# Motors.net
KiCad netlist of a schematic drawn in Altium Designer
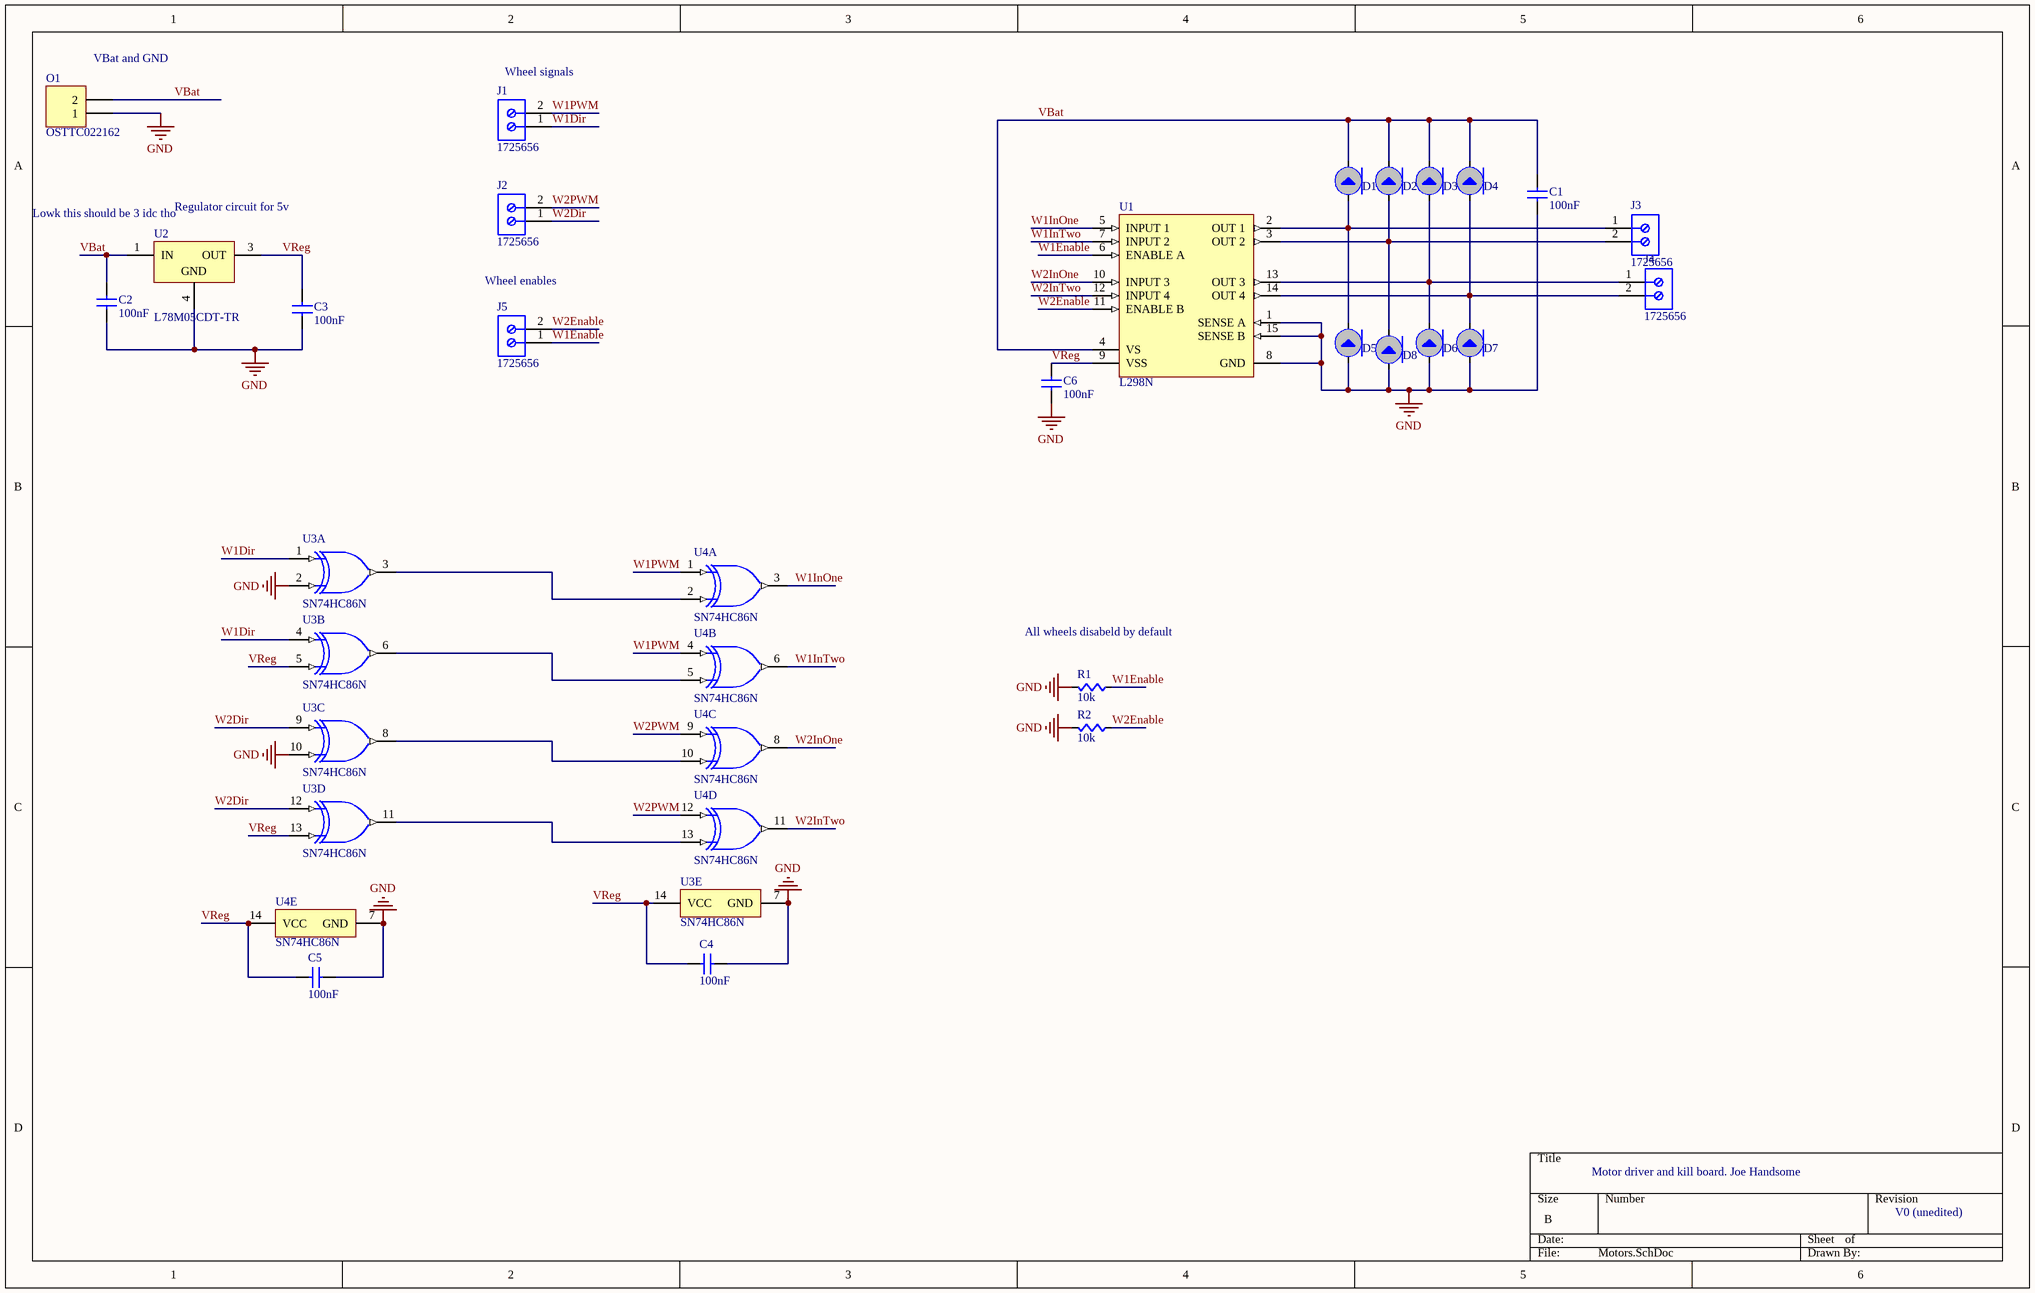
[diagram p0: Motors.SchDoc]

(export (version "E")
  (design (tool "Eeschema 10.0.6"))
  (components
    (comp (ref "C1")
      (value "100nF")
      (footprint "CAPC0603")
      (fields (field (name "Comment") "Cap"))
      (libsource (lib "Passives") (part "Cap"))
    )
    (comp (ref "C2")
      (value "100nF")
      (footprint "CAPC0603")
      (fields (field (name "Comment") "Cap"))
      (libsource (lib "Passives") (part "Cap"))
    )
    (comp (ref "C3")
      (value "100nF")
      (footprint "CAPC0603")
      (fields (field (name "Comment") "Cap"))
      (libsource (lib "Passives") (part "Cap"))
    )
    (comp (ref "C4")
      (value "100nF")
      (footprint "CAPC0603")
      (fields (field (name "Comment") "Cap"))
      (libsource (lib "Passives") (part "Cap"))
    )
    (comp (ref "C5")
      (value "100nF")
      (footprint "CAPC0603")
      (fields (field (name "Comment") "Cap"))
      (libsource (lib "Passives") (part "Cap"))
    )
    (comp (ref "C6")
      (value "100nF")
      (footprint "CAPC0603")
      (fields (field (name "Comment") "Cap"))
      (libsource (lib "Passives") (part "Cap"))
    )
    (comp (ref "D1")
      (value "Diode")
      (footprint "MBRS360SMB")
      (description "Standard Diode Template")
      (libsource (lib "Semiconductors") (part "Diode"))
    )
    (comp (ref "D2")
      (value "Diode")
      (footprint "MBRS360SMB")
      (description "Standard Diode Template")
      (libsource (lib "Semiconductors") (part "Diode"))
    )
    (comp (ref "D3")
      (value "Diode")
      (footprint "MBRS360SMB")
      (description "Standard Diode Template")
      (libsource (lib "Semiconductors") (part "Diode"))
    )
    (comp (ref "D4")
      (value "Diode")
      (footprint "MBRS360SMB")
      (description "Standard Diode Template")
      (libsource (lib "Semiconductors") (part "Diode"))
    )
    (comp (ref "D5")
      (value "Diode")
      (footprint "MBRS360SMB")
      (description "Standard Diode Template")
      (libsource (lib "Semiconductors") (part "Diode"))
    )
    (comp (ref "D6")
      (value "Diode")
      (footprint "MBRS360SMB")
      (description "Standard Diode Template")
      (libsource (lib "Semiconductors") (part "Diode"))
    )
    (comp (ref "D7")
      (value "Diode")
      (footprint "MBRS360SMB")
      (description "Standard Diode Template")
      (libsource (lib "Semiconductors") (part "Diode"))
    )
    (comp (ref "D8")
      (value "Diode")
      (footprint "MBRS360SMB")
      (description "Standard Diode Template")
      (libsource (lib "Semiconductors") (part "Diode"))
    )
    (comp (ref "J1")
      (value "1725656")
      (footprint "PHOE-1725656-2")
      (description "Male Header, Pitch 2.54 mm, 1 x 2 Position, Height 9 mm, Tail Length 3.5 mm")
      (fields (field (name "MANUFACTURER") "Phoenix Contact"))
      (libsource (lib "Altium Content Vault") (part "CN-1P-F-TB2"))
    )
    (comp (ref "J2")
      (value "1725656")
      (footprint "PHOE-1725656-2")
      (description "Male Header, Pitch 2.54 mm, 1 x 2 Position, Height 9 mm, Tail Length 3.5 mm")
      (fields (field (name "MANUFACTURER") "Phoenix Contact"))
      (libsource (lib "Altium Content Vault") (part "CN-1P-F-TB2"))
    )
    (comp (ref "J3")
      (value "1725656")
      (footprint "PHOE-1725656-2")
      (description "Male Header, Pitch 2.54 mm, 1 x 2 Position, Height 9 mm, Tail Length 3.5 mm")
      (fields (field (name "MANUFACTURER") "Phoenix Contact"))
      (libsource (lib "Altium Content Vault") (part "CN-1P-F-TB2"))
    )
    (comp (ref "J4")
      (value "1725656")
      (footprint "PHOE-1725656-2")
      (description "Male Header, Pitch 2.54 mm, 1 x 2 Position, Height 9 mm, Tail Length 3.5 mm")
      (fields (field (name "MANUFACTURER") "Phoenix Contact"))
      (libsource (lib "Altium Content Vault") (part "CN-1P-F-TB2"))
    )
    (comp (ref "J5")
      (value "1725656")
      (footprint "PHOE-1725656-2")
      (description "Male Header, Pitch 2.54 mm, 1 x 2 Position, Height 9 mm, Tail Length 3.5 mm")
      (fields (field (name "MANUFACTURER") "Phoenix Contact"))
      (libsource (lib "Altium Content Vault") (part "CN-1P-F-TB2"))
    )
    (comp (ref "O1")
      (value "OSTTC022162")
      (footprint "high_amp_conn")
      (description "Terminal Block Header 2-Position Top Screw 0.200\" (5.08mm) PC-Pins")
      (fields (field (name "MANUFACTURER") "On-Shore Technology") (field (name "VOLTAGE") "300V"))
      (libsource (lib "Schlib1") (part "OSTTC022162"))
    )
    (comp (ref "R1")
      (value "10k")
      (footprint "RES0603")
      (fields (field (name "Comment") "Res"))
      (libsource (lib "Passives") (part "Res"))
    )
    (comp (ref "R2")
      (value "10k")
      (footprint "RES0603")
      (fields (field (name "Comment") "Res"))
      (libsource (lib "Passives") (part "Res"))
    )
    (comp (ref "U1")
      (value "L298N")
      (footprint "STM-FM-15")
      (description "Dual Full-Bridge Driver, 4.8 to 46 V, -40 to 150 degC, 15-Pin FM (MW 15L), RoHS, Tube")
      (fields (field (name "MANUFACTURER") "STMicroelectronics") (field (name "PARTNUMBER") "L298"))
      (libsource (lib "Altium Content Vault") (part "STM-L298-15"))
    )
    (comp (ref "U2")
      (value "L78M05CDT-TR")
      (footprint "TO-252_L")
      (description "Positive Voltage Regulator, 5V, 3-Pin DPAK, Tape and Reel")
      (libsource (lib "Altium Content Vault") (part "PM-REG-L4940-SOT3"))
    )
    (comp (ref "U3")
      (value "SN74HC86N")
      (footprint "PCBComponent_1")
      (description "Quadruple 2-Input Exclusive-OR Gates, N0014A, TUBE")
      (fields
        (field (name "MANUFACTURER") "Texas Instruments")
        (field (name "GENERIC PART NUMBER") "SN74HC86")
      )
      (libsource (lib "Schlib1") (part "CMP-0778-00109-3"))
    )
    (comp (ref "U4")
      (value "SN74HC86N")
      (footprint "PCBComponent_1")
      (description "Quadruple 2-Input Exclusive-OR Gates, N0014A, TUBE")
      (fields
        (field (name "MANUFACTURER") "Texas Instruments")
        (field (name "GENERIC PART NUMBER") "SN74HC86")
      )
      (libsource (lib "Schlib1") (part "CMP-0778-00109-3"))
    )
  )
  (nets
    (net (code "1") (name "/VBat") (class "Default")
      (node (ref "C1") (pin "1") (pinfunction "A_1") (pintype "passive"))
      (node (ref "C2") (pin "1") (pinfunction "A_1") (pintype "passive"))
      (node (ref "D1") (pin "C") (pinfunction "C_C") (pintype "passive"))
      (node (ref "D2") (pin "C") (pinfunction "C_C") (pintype "passive"))
      (node (ref "D3") (pin "C") (pinfunction "C_C") (pintype "passive"))
      (node (ref "D4") (pin "C") (pinfunction "C_C") (pintype "passive"))
      (node (ref "O1") (pin "2") (pinfunction "2_2") (pintype "passive"))
      (node (ref "U1") (pin "4") (pinfunction "VS_4") (pintype "power_in"))
      (node (ref "U2") (pin "1") (pinfunction "IN_1") (pintype "power_in"))
    )
    (net (code "2") (name "/VReg") (class "Default")
      (node (ref "C3") (pin "1") (pinfunction "A_1") (pintype "passive"))
      (node (ref "C4") (pin "1") (pinfunction "A_1") (pintype "passive"))
      (node (ref "C5") (pin "1") (pinfunction "A_1") (pintype "passive"))
      (node (ref "C6") (pin "1") (pinfunction "A_1") (pintype "passive"))
      (node (ref "U1") (pin "9") (pinfunction "VSS_9") (pintype "power_in"))
      (node (ref "U2") (pin "3") (pinfunction "OUT_3") (pintype "power_in"))
      (node (ref "U3") (pin "13") (pinfunction "4B_13") (pintype "input"))
      (node (ref "U3") (pin "14") (pinfunction "VCC_14") (pintype "power_in"))
      (node (ref "U3") (pin "5") (pinfunction "2B_5") (pintype "input"))
      (node (ref "U4") (pin "14") (pinfunction "VCC_14") (pintype "power_in"))
    )
    (net (code "3") (name "/W1Dir") (class "Default")
      (node (ref "J1") (pin "1") (pinfunction "1_1") (pintype "passive"))
      (node (ref "U3") (pin "1") (pinfunction "1A_1") (pintype "input"))
      (node (ref "U3") (pin "4") (pinfunction "2A_4") (pintype "input"))
    )
    (net (code "4") (name "/W1Enable") (class "Default")
      (node (ref "J5") (pin "1") (pinfunction "1_1") (pintype "passive"))
      (node (ref "R1") (pin "2") (pinfunction "B_2") (pintype "passive"))
      (node (ref "U1") (pin "6") (pinfunction "ENABLE_A_6") (pintype "input"))
    )
    (net (code "5") (name "/W1InOne") (class "Default")
      (node (ref "U1") (pin "5") (pinfunction "INPUT_1_5") (pintype "input"))
      (node (ref "U4") (pin "3") (pinfunction "1Y_3") (pintype "output"))
    )
    (net (code "6") (name "/W1InTwo") (class "Default")
      (node (ref "U1") (pin "7") (pinfunction "INPUT_2_7") (pintype "input"))
      (node (ref "U4") (pin "6") (pinfunction "2Y_6") (pintype "output"))
    )
    (net (code "7") (name "/W1PWM") (class "Default")
      (node (ref "J1") (pin "2") (pinfunction "2_2") (pintype "passive"))
      (node (ref "U4") (pin "1") (pinfunction "1A_1") (pintype "input"))
      (node (ref "U4") (pin "4") (pinfunction "2A_4") (pintype "input"))
    )
    (net (code "8") (name "/W2Dir") (class "Default")
      (node (ref "J2") (pin "1") (pinfunction "1_1") (pintype "passive"))
      (node (ref "U3") (pin "12") (pinfunction "4A_12") (pintype "input"))
      (node (ref "U3") (pin "9") (pinfunction "3A_9") (pintype "input"))
    )
    (net (code "9") (name "/W2Enable") (class "Default")
      (node (ref "J5") (pin "2") (pinfunction "2_2") (pintype "passive"))
      (node (ref "R2") (pin "2") (pinfunction "B_2") (pintype "passive"))
      (node (ref "U1") (pin "11") (pinfunction "ENABLE_B_11") (pintype "input"))
    )
    (net (code "10") (name "/W2InOne") (class "Default")
      (node (ref "U1") (pin "10") (pinfunction "INPUT_3_10") (pintype "input"))
      (node (ref "U4") (pin "8") (pinfunction "3Y_8") (pintype "output"))
    )
    (net (code "11") (name "/W2InTwo") (class "Default")
      (node (ref "U1") (pin "12") (pinfunction "INPUT_4_12") (pintype "input"))
      (node (ref "U4") (pin "11") (pinfunction "4Y_11") (pintype "output"))
    )
    (net (code "12") (name "/W2PWM") (class "Default")
      (node (ref "J2") (pin "2") (pinfunction "2_2") (pintype "passive"))
      (node (ref "U4") (pin "12") (pinfunction "4A_12") (pintype "input"))
      (node (ref "U4") (pin "9") (pinfunction "3A_9") (pintype "input"))
    )
    (net (code "13") (name "GND") (class "Default")
      (node (ref "C1") (pin "2") (pinfunction "B_2") (pintype "passive"))
      (node (ref "C2") (pin "2") (pinfunction "B_2") (pintype "passive"))
      (node (ref "C3") (pin "2") (pinfunction "B_2") (pintype "passive"))
      (node (ref "C4") (pin "2") (pinfunction "B_2") (pintype "passive"))
      (node (ref "C5") (pin "2") (pinfunction "B_2") (pintype "passive"))
      (node (ref "C6") (pin "2") (pinfunction "B_2") (pintype "passive"))
      (node (ref "D5") (pin "A") (pinfunction "A_A") (pintype "passive"))
      (node (ref "D6") (pin "A") (pinfunction "A_A") (pintype "passive"))
      (node (ref "D7") (pin "A") (pinfunction "A_A") (pintype "passive"))
      (node (ref "D8") (pin "A") (pinfunction "A_A") (pintype "passive"))
      (node (ref "O1") (pin "1") (pinfunction "1_1") (pintype "passive"))
      (node (ref "R1") (pin "1") (pinfunction "A_1") (pintype "passive"))
      (node (ref "R2") (pin "1") (pinfunction "A_1") (pintype "passive"))
      (node (ref "U1") (pin "1") (pinfunction "SENSE_A_1") (pintype "input"))
      (node (ref "U1") (pin "15") (pinfunction "SENSE_B_15") (pintype "input"))
      (node (ref "U1") (pin "8") (pinfunction "GND_8") (pintype "power_in"))
      (node (ref "U2") (pin "4") (pinfunction "GND_4") (pintype "power_in"))
      (node (ref "U3") (pin "10") (pinfunction "3B_10") (pintype "input"))
      (node (ref "U3") (pin "2") (pinfunction "1B_2") (pintype "input"))
      (node (ref "U3") (pin "7") (pinfunction "GND_7") (pintype "power_in"))
      (node (ref "U4") (pin "7") (pinfunction "GND_7") (pintype "power_in"))
    )
    (net (code "14") (name "Net-(U1-OUT_1)") (class "Default")
      (node (ref "D1") (pin "A") (pinfunction "A_A") (pintype "passive"))
      (node (ref "D5") (pin "C") (pinfunction "C_C") (pintype "passive"))
      (node (ref "J3") (pin "1") (pinfunction "1_1") (pintype "passive"))
      (node (ref "U1") (pin "2") (pinfunction "OUT_1_2") (pintype "output"))
    )
    (net (code "15") (name "Net-(U1-OUT_2)") (class "Default")
      (node (ref "D2") (pin "A") (pinfunction "A_A") (pintype "passive"))
      (node (ref "D8") (pin "C") (pinfunction "C_C") (pintype "passive"))
      (node (ref "J3") (pin "2") (pinfunction "2_2") (pintype "passive"))
      (node (ref "U1") (pin "3") (pinfunction "OUT_2_3") (pintype "output"))
    )
    (net (code "16") (name "Net-(U1-OUT_3)") (class "Default")
      (node (ref "D3") (pin "A") (pinfunction "A_A") (pintype "passive"))
      (node (ref "D6") (pin "C") (pinfunction "C_C") (pintype "passive"))
      (node (ref "J4") (pin "1") (pinfunction "1_1") (pintype "passive"))
      (node (ref "U1") (pin "13") (pinfunction "OUT_3_13") (pintype "output"))
    )
    (net (code "17") (name "Net-(U1-OUT_4)") (class "Default")
      (node (ref "D4") (pin "A") (pinfunction "A_A") (pintype "passive"))
      (node (ref "D7") (pin "C") (pinfunction "C_C") (pintype "passive"))
      (node (ref "J4") (pin "2") (pinfunction "2_2") (pintype "passive"))
      (node (ref "U1") (pin "14") (pinfunction "OUT_4_14") (pintype "output"))
    )
    (net (code "18") (name "Net-(U3A-1Y)") (class "Default")
      (node (ref "U3") (pin "3") (pinfunction "1Y_3") (pintype "output"))
      (node (ref "U4") (pin "2") (pinfunction "1B_2") (pintype "input"))
    )
    (net (code "19") (name "Net-(U3B-2Y)") (class "Default")
      (node (ref "U3") (pin "6") (pinfunction "2Y_6") (pintype "output"))
      (node (ref "U4") (pin "5") (pinfunction "2B_5") (pintype "input"))
    )
    (net (code "20") (name "Net-(U3C-3Y)") (class "Default")
      (node (ref "U3") (pin "8") (pinfunction "3Y_8") (pintype "output"))
      (node (ref "U4") (pin "10") (pinfunction "3B_10") (pintype "input"))
    )
    (net (code "21") (name "Net-(U3D-4Y)") (class "Default")
      (node (ref "U3") (pin "11") (pinfunction "4Y_11") (pintype "output"))
      (node (ref "U4") (pin "13") (pinfunction "4B_13") (pintype "input"))
    )
  )
)
